# FanControllerv11.net
KiCad netlist of a schematic drawn in EAGLE
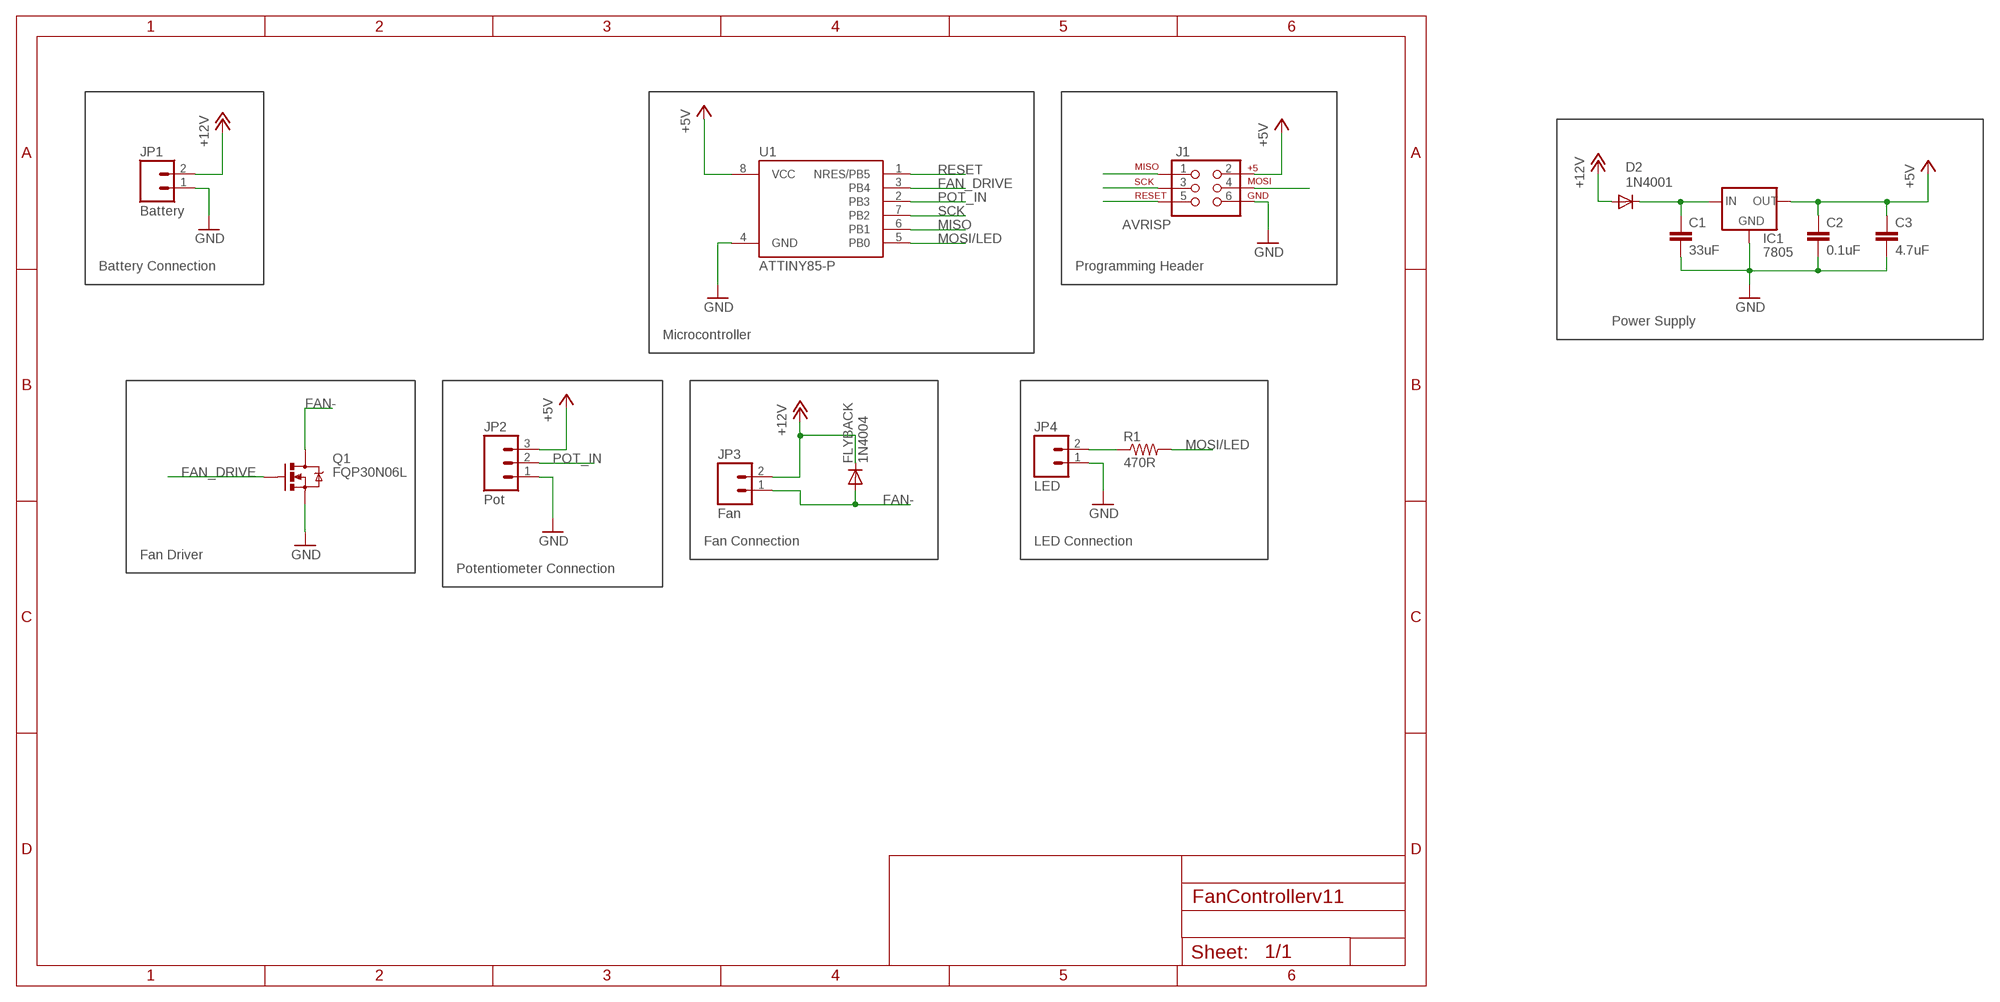
[diagram p0: schematic, sheet 1]

(export (version "E")
  (design (tool "Eeschema 10.0.6"))
  (components
    (comp (ref "C1")
      (value "33uF")
      (footprint "eagle-import:CAP-PTH-SMALL")
      (libsource (lib "eagle-import") (part "CAPPTH"))
    )
    (comp (ref "C2")
      (value "0.1uF")
      (footprint "eagle-import:CAP-PTH-LARGE")
      (libsource (lib "eagle-import") (part "CAPPTH3"))
    )
    (comp (ref "C3")
      (value "4.7uF")
      (footprint "eagle-import:CAP-PTH-SMALL")
      (libsource (lib "eagle-import") (part "CAPPTH"))
    )
    (comp (ref "D2")
      (value "1N4001")
      (footprint "eagle-import:DIODE-1N4148")
      (libsource (lib "eagle-import") (part "DIODE1N4148"))
    )
    (comp (ref "FLYBACK")
      (value "1N4004")
      (footprint "eagle-import:DIODE-1N4148")
      (libsource (lib "eagle-import") (part "DIODE1N4148"))
    )
    (comp (ref "IC1")
      (value "7805")
      (footprint "eagle-import:78XXL")
      (libsource (lib "eagle-import") (part "V_REG_78XXSIDE"))
    )
    (comp (ref "J1")
      (value "AVRISP")
      (footprint "eagle-import:2X3")
      (libsource (lib "eagle-import") (part "AVR_SPI_PRG_6PTH"))
    )
    (comp (ref "JP1")
      (value "Battery")
      (footprint "eagle-import:1X02_XTRA_BIG")
      (libsource (lib "eagle-import") (part "M02PTH4"))
    )
    (comp (ref "JP2")
      (value "Pot")
      (footprint "eagle-import:MOLEX-1X3")
      (libsource (lib "eagle-import") (part "M03POLAR"))
    )
    (comp (ref "JP3")
      (value "Fan")
      (footprint "eagle-import:1X02_XTRA_BIG")
      (libsource (lib "eagle-import") (part "M02PTH4"))
    )
    (comp (ref "JP4")
      (value "LED")
      (footprint "eagle-import:MOLEX-1X2")
      (libsource (lib "eagle-import") (part "M02POLAR"))
    )
    (comp (ref "Q1")
      (value "FQP30N06L")
      (footprint "eagle-import:TO220V")
      (libsource (lib "eagle-import") (part "MOSFET-NCHANNELFQP30N06L"))
    )
    (comp (ref "R1")
      (value "470R")
      (footprint "eagle-import:AXIAL-0.3")
      (libsource (lib "eagle-import") (part "RESISTORAXIAL-0.3"))
    )
    (comp (ref "U1")
      (value "ATTINY85-P")
      (footprint "eagle-import:PDIP08_300MIL")
      (libsource (lib "eagle-import") (part "ATTINY85P-"))
    )
  )
  (nets
    (net (code "1") (name "+5V") (class "Default")
      (node (ref "C2") (pin "1") (pinfunction "1_1") (pintype "passive"))
      (node (ref "C3") (pin "1") (pinfunction "1_1") (pintype "passive"))
      (node (ref "IC1") (pin "OUT") (pinfunction "OUT_OUT") (pintype "output"))
      (node (ref "J1") (pin "2") (pinfunction "2_2") (pintype "passive"))
      (node (ref "JP2") (pin "3") (pinfunction "3_3") (pintype "passive"))
      (node (ref "U1") (pin "8") (pinfunction "VCC_8") (pintype "power_in"))
    )
    (net (code "2") (name "+12V") (class "Default")
      (node (ref "D2") (pin "A") (pinfunction "A_A") (pintype "passive"))
      (node (ref "FLYBACK") (pin "C") (pinfunction "C_C") (pintype "passive"))
      (node (ref "JP1") (pin "2") (pinfunction "2_2") (pintype "passive"))
      (node (ref "JP3") (pin "2") (pinfunction "2_2") (pintype "passive"))
    )
    (net (code "3") (name "/FAN-") (class "Default")
      (node (ref "FLYBACK") (pin "A") (pinfunction "A_A") (pintype "passive"))
      (node (ref "JP3") (pin "1") (pinfunction "1_1") (pintype "passive"))
      (node (ref "Q1") (pin "2") (pinfunction "D_2") (pintype "passive"))
    )
    (net (code "4") (name "/FAN_DRIVE") (class "Default")
      (node (ref "Q1") (pin "1") (pinfunction "G_1") (pintype "passive"))
      (node (ref "U1") (pin "3") (pinfunction "PB4_3") (pintype "bidirectional"))
    )
    (net (code "5") (name "/MISO") (class "Default")
      (node (ref "J1") (pin "1") (pinfunction "1_1") (pintype "passive"))
      (node (ref "U1") (pin "6") (pinfunction "PB1_6") (pintype "bidirectional"))
    )
    (net (code "6") (name "/MOSI{slash}LED") (class "Default")
      (node (ref "J1") (pin "4") (pinfunction "4_4") (pintype "passive"))
      (node (ref "R1") (pin "P$2") (pinfunction "2_P$2") (pintype "passive"))
      (node (ref "U1") (pin "5") (pinfunction "PB0_5") (pintype "bidirectional"))
    )
    (net (code "7") (name "/POT_IN") (class "Default")
      (node (ref "JP2") (pin "2") (pinfunction "2_2") (pintype "passive"))
      (node (ref "U1") (pin "2") (pinfunction "PB3_2") (pintype "bidirectional"))
    )
    (net (code "8") (name "/RESET") (class "Default")
      (node (ref "J1") (pin "5") (pinfunction "5_5") (pintype "passive"))
      (node (ref "U1") (pin "1") (pinfunction "NRES/PB5_1") (pintype "bidirectional"))
    )
    (net (code "9") (name "/SCK") (class "Default")
      (node (ref "J1") (pin "3") (pinfunction "3_3") (pintype "passive"))
      (node (ref "U1") (pin "7") (pinfunction "PB2_7") (pintype "bidirectional"))
    )
    (net (code "10") (name "GND") (class "Default")
      (node (ref "C1") (pin "2") (pinfunction "2_2") (pintype "passive"))
      (node (ref "C2") (pin "2") (pinfunction "2_2") (pintype "passive"))
      (node (ref "C3") (pin "2") (pinfunction "2_2") (pintype "passive"))
      (node (ref "IC1") (pin "GND") (pinfunction "GND_GND") (pintype "input"))
      (node (ref "J1") (pin "6") (pinfunction "6_6") (pintype "passive"))
      (node (ref "JP1") (pin "1") (pinfunction "1_1") (pintype "passive"))
      (node (ref "JP2") (pin "1") (pinfunction "1_1") (pintype "passive"))
      (node (ref "JP4") (pin "1") (pinfunction "1_1") (pintype "passive"))
      (node (ref "Q1") (pin "3") (pinfunction "S_3") (pintype "passive"))
      (node (ref "U1") (pin "4") (pinfunction "GND_4") (pintype "power_in"))
    )
    (net (code "11") (name "Net-(C1-Pad1)") (class "Default")
      (node (ref "C1") (pin "1") (pinfunction "1_1") (pintype "passive"))
      (node (ref "D2") (pin "C") (pinfunction "C_C") (pintype "passive"))
      (node (ref "IC1") (pin "IN") (pinfunction "IN_IN") (pintype "input"))
    )
    (net (code "12") (name "Net-(R1-1)") (class "Default")
      (node (ref "JP4") (pin "2") (pinfunction "2_2") (pintype "passive"))
      (node (ref "R1") (pin "P$1") (pinfunction "1_P$1") (pintype "passive"))
    )
  )
)
